# ATTiny85_5LED_R2.net
KiCad netlist of a schematic drawn in EAGLE
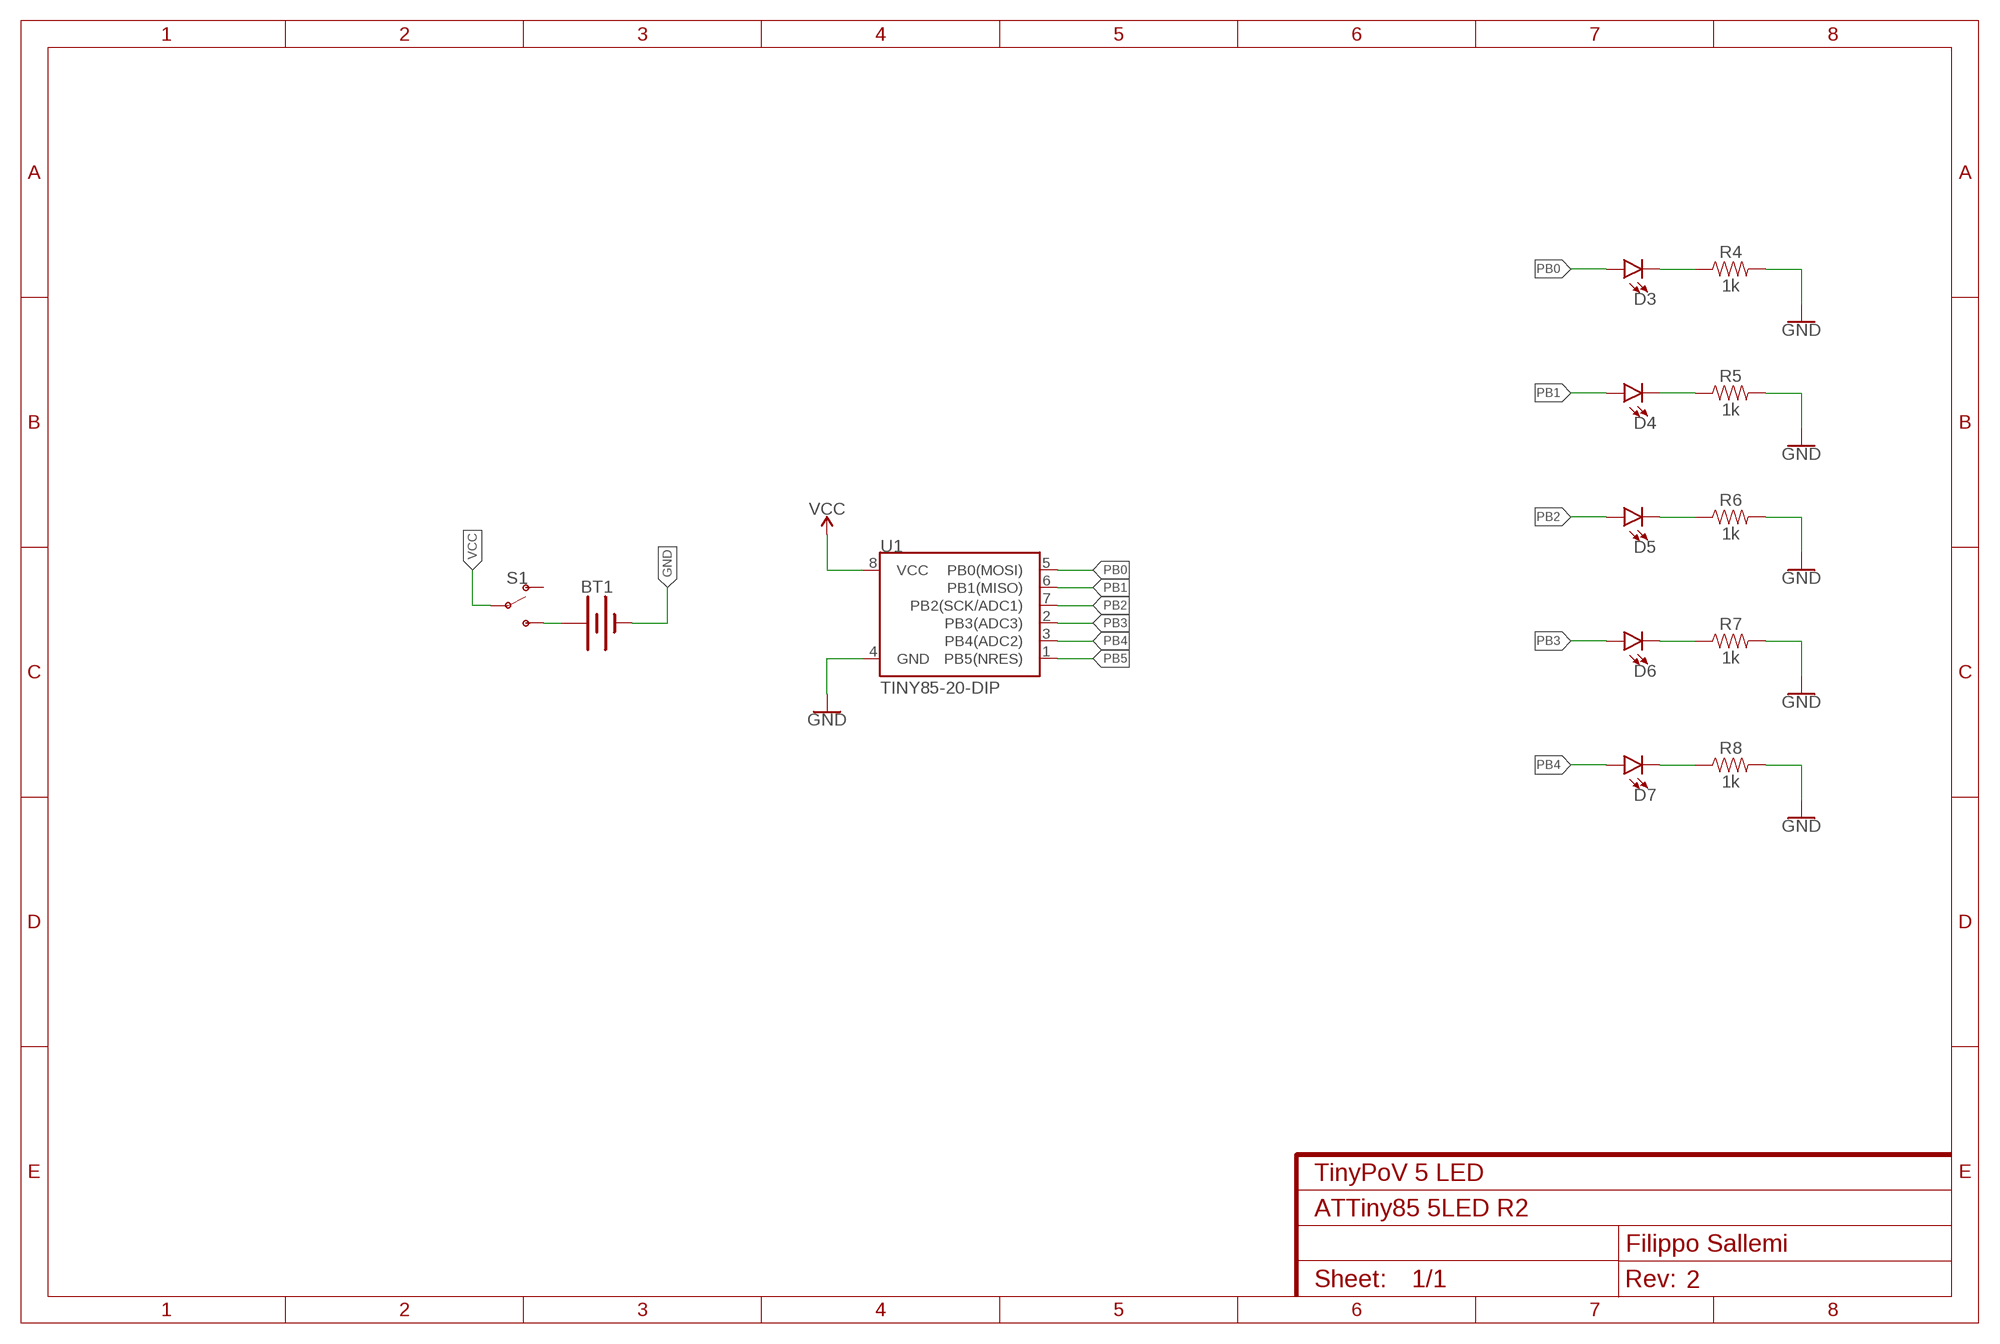
[diagram p0: schematic, sheet 1]

(export (version "E")
  (design (tool "Eeschema 10.0.6"))
  (components
    (comp (ref "BT1")
      (value "BATTERY-12MM_PTH")
      (footprint "eagle-import:BATTCON_12MM_PTH")
      (libsource (lib "eagle-import") (part "BATTERY-12MM_PTH"))
    )
    (comp (ref "D3")
      (value "LED5MM")
      (footprint "eagle-import:LED_5MM")
      (libsource (lib "eagle-import") (part "LED5MM"))
    )
    (comp (ref "D4")
      (value "LED5MM")
      (footprint "eagle-import:LED_5MM")
      (libsource (lib "eagle-import") (part "LED5MM"))
    )
    (comp (ref "D5")
      (value "LED5MM")
      (footprint "eagle-import:LED_5MM")
      (libsource (lib "eagle-import") (part "LED5MM"))
    )
    (comp (ref "D6")
      (value "LED5MM")
      (footprint "eagle-import:LED_5MM")
      (libsource (lib "eagle-import") (part "LED5MM"))
    )
    (comp (ref "D7")
      (value "LED5MM")
      (footprint "eagle-import:LED_5MM")
      (libsource (lib "eagle-import") (part "LED5MM"))
    )
    (comp (ref "R4")
      (value "1k")
      (footprint "eagle-import:AXIAL-0.3")
      (libsource (lib "eagle-import") (part "1KOHM-HORIZ-1/4W-5%"))
    )
    (comp (ref "R5")
      (value "1k")
      (footprint "eagle-import:AXIAL-0.3")
      (libsource (lib "eagle-import") (part "1KOHM-HORIZ-1/4W-5%"))
    )
    (comp (ref "R6")
      (value "1k")
      (footprint "eagle-import:AXIAL-0.3")
      (libsource (lib "eagle-import") (part "1KOHM-HORIZ-1/4W-5%"))
    )
    (comp (ref "R7")
      (value "1k")
      (footprint "eagle-import:AXIAL-0.3")
      (libsource (lib "eagle-import") (part "1KOHM-HORIZ-1/4W-5%"))
    )
    (comp (ref "R8")
      (value "1k")
      (footprint "eagle-import:AXIAL-0.3")
      (libsource (lib "eagle-import") (part "1KOHM-HORIZ-1/4W-5%"))
    )
    (comp (ref "S1")
      (value "SWITCH-SPDT-PTH-11.6X4.0MM-KIT")
      (footprint "eagle-import:SWITCH_SPDT_PTH_11.6X4.0MM_KIT")
      (libsource (lib "eagle-import") (part "SWITCH-SPDT-PTH-11.6X4.0MM-KIT"))
    )
    (comp (ref "U1")
      (value "TINY85-20-DIP")
      (footprint "eagle-import:DIP08_MCU")
      (libsource (lib "eagle-import") (part "ATTINY45TINY85-20-DIP"))
    )
  )
  (nets
    (net (code "1") (name "GND") (class "Default")
      (node (ref "BT1") (pin "GND") (pinfunction "-_GND") (pintype "power_in"))
      (node (ref "R4") (pin "P$2") (pinfunction "2_P$2") (pintype "passive"))
      (node (ref "R5") (pin "P$2") (pinfunction "2_P$2") (pintype "passive"))
      (node (ref "R6") (pin "P$2") (pinfunction "2_P$2") (pintype "passive"))
      (node (ref "R7") (pin "P$2") (pinfunction "2_P$2") (pintype "passive"))
      (node (ref "R8") (pin "P$2") (pinfunction "2_P$2") (pintype "passive"))
      (node (ref "U1") (pin "4") (pinfunction "GND_4") (pintype "bidirectional"))
    )
    (net (code "2") (name "Net-(BT1-+)") (class "Default")
      (node (ref "BT1") (pin "VCC@1") (pinfunction "+_VCC@1") (pintype "power_in"))
      (node (ref "S1") (pin "3") (pinfunction "S_3") (pintype "passive"))
    )
    (net (code "3") (name "Net-(D3-C)") (class "Default")
      (node (ref "D3") (pin "K") (pinfunction "C_K") (pintype "passive"))
      (node (ref "R4") (pin "P$1") (pinfunction "1_P$1") (pintype "passive"))
    )
    (net (code "4") (name "Net-(D4-C)") (class "Default")
      (node (ref "D4") (pin "K") (pinfunction "C_K") (pintype "passive"))
      (node (ref "R5") (pin "P$1") (pinfunction "1_P$1") (pintype "passive"))
    )
    (net (code "5") (name "Net-(D5-C)") (class "Default")
      (node (ref "D5") (pin "K") (pinfunction "C_K") (pintype "passive"))
      (node (ref "R6") (pin "P$1") (pinfunction "1_P$1") (pintype "passive"))
    )
    (net (code "6") (name "Net-(D6-C)") (class "Default")
      (node (ref "D6") (pin "K") (pinfunction "C_K") (pintype "passive"))
      (node (ref "R7") (pin "P$1") (pinfunction "1_P$1") (pintype "passive"))
    )
    (net (code "7") (name "Net-(D7-C)") (class "Default")
      (node (ref "D7") (pin "K") (pinfunction "C_K") (pintype "passive"))
      (node (ref "R8") (pin "P$1") (pinfunction "1_P$1") (pintype "passive"))
    )
    (net (code "8") (name "PB0") (class "Default")
      (node (ref "D3") (pin "A") (pinfunction "A_A") (pintype "passive"))
      (node (ref "U1") (pin "5") (pinfunction "PB0(MOSI)_5") (pintype "bidirectional"))
    )
    (net (code "9") (name "PB1") (class "Default")
      (node (ref "D4") (pin "A") (pinfunction "A_A") (pintype "passive"))
      (node (ref "U1") (pin "6") (pinfunction "PB1(MISO)_6") (pintype "bidirectional"))
    )
    (net (code "10") (name "PB2") (class "Default")
      (node (ref "D5") (pin "A") (pinfunction "A_A") (pintype "passive"))
      (node (ref "U1") (pin "7") (pinfunction "PB2(SCK/ADC1)_7") (pintype "bidirectional"))
    )
    (net (code "11") (name "PB3") (class "Default")
      (node (ref "D6") (pin "A") (pinfunction "A_A") (pintype "passive"))
      (node (ref "U1") (pin "2") (pinfunction "PB3(ADC3)_2") (pintype "bidirectional"))
    )
    (net (code "12") (name "PB4") (class "Default")
      (node (ref "D7") (pin "A") (pinfunction "A_A") (pintype "passive"))
      (node (ref "U1") (pin "3") (pinfunction "PB4(ADC2)_3") (pintype "bidirectional"))
    )
    (net (code "13") (name "PB5") (class "Default")
      (node (ref "U1") (pin "1") (pinfunction "PB5(NRES)_1") (pintype "bidirectional"))
    )
    (net (code "14") (name "VCC") (class "Default")
      (node (ref "S1") (pin "2") (pinfunction "P_2") (pintype "passive"))
      (node (ref "U1") (pin "8") (pinfunction "VCC_8") (pintype "bidirectional"))
    )
    (net (code "15") (name "unconnected-(S1-O-Pad1)") (class "Default")
      (node (ref "S1") (pin "1") (pinfunction "O_1") (pintype "passive"))
    )
  )
)
